# dmxisolator-mod-v1a.net
KiCad netlist of a schematic drawn in EAGLE
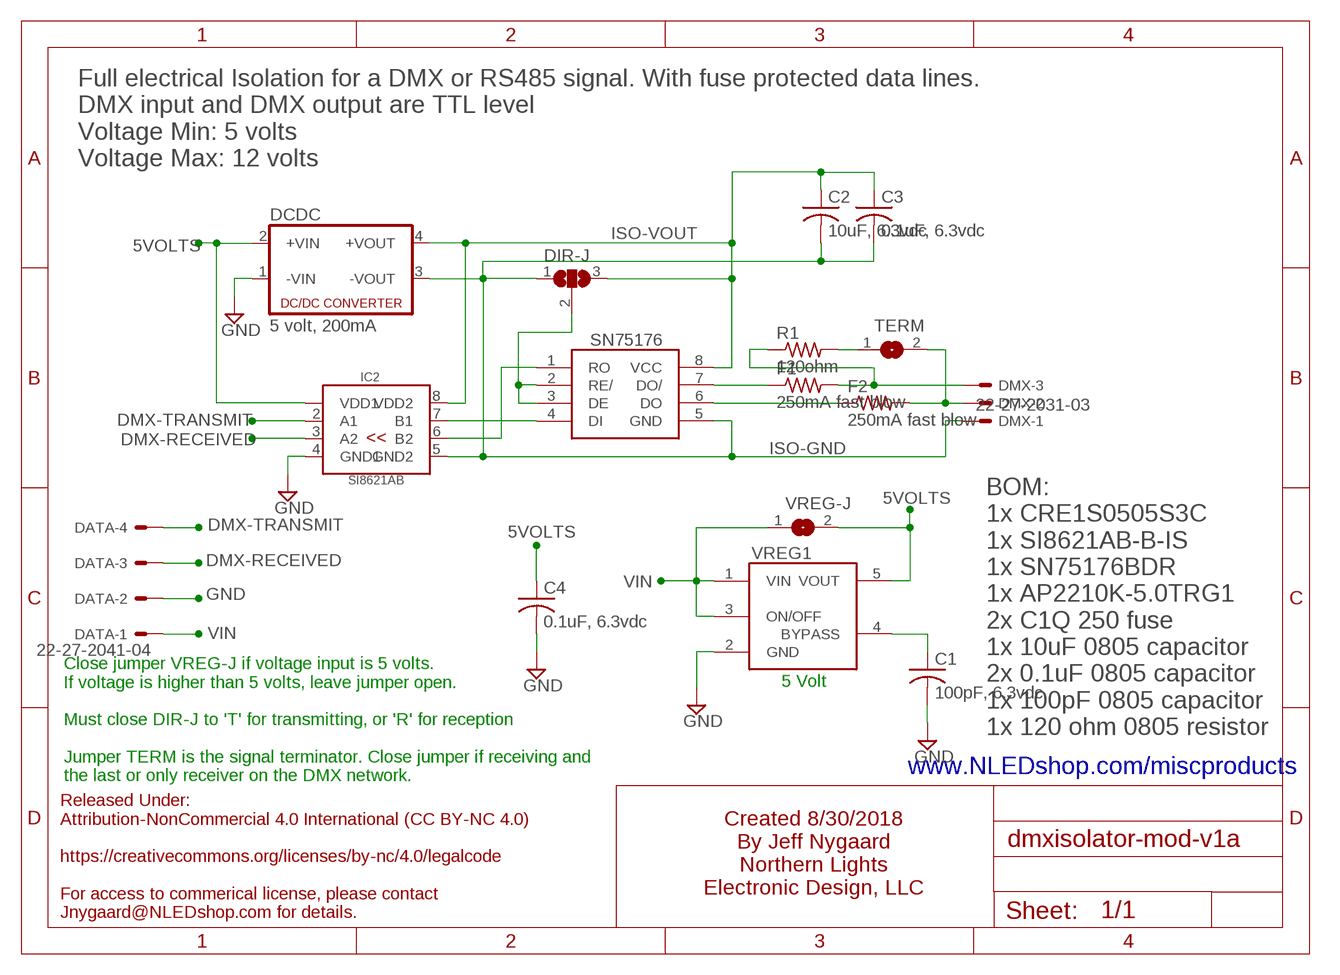
[diagram p0: schematic, sheet 1]

(export (version "E")
  (design (tool "Eeschema 10.0.6"))
  (components
    (comp (ref "C1")
      (value "100pF, 6.3vdc")
      (footprint "eagle-import:C0805")
      (libsource (lib "eagle-import") (part "C-USC0805"))
    )
    (comp (ref "C2")
      (value "10uF, 6.3vdc")
      (footprint "eagle-import:C0805")
      (libsource (lib "eagle-import") (part "C-USC0805"))
    )
    (comp (ref "C3")
      (value "0.1uF, 6.3vdc")
      (footprint "eagle-import:C0805")
      (libsource (lib "eagle-import") (part "C-USC0805"))
    )
    (comp (ref "C4")
      (value "0.1uF, 6.3vdc")
      (footprint "eagle-import:C0805")
      (libsource (lib "eagle-import") (part "C-USC0805"))
    )
    (comp (ref "DATA")
      (value "22-27-2041-04")
      (footprint "eagle-import:6410-04")
      (fields (field (name "MF") "MOLEX"))
      (libsource (lib "eagle-import") (part "22-?-0427-2041"))
    )
    (comp (ref "DCDC")
      (value "5 volt, 200mA")
      (footprint "eagle-import:NME")
      (fields (field (name "MF") "C & D TECHNOLOGIES, INC") (field (name "MPN") "NME1205D"))
      (libsource (lib "eagle-import") (part "NME"))
    )
    (comp (ref "DIR-J")
      (value "SJ2W")
      (footprint "eagle-import:SJ_2")
      (libsource (lib "eagle-import") (part "SJ2W"))
    )
    (comp (ref "DMX")
      (value "22-27-2031-03")
      (footprint "eagle-import:6410-03")
      (fields (field (name "MF") "MOLEX"))
      (libsource (lib "eagle-import") (part "22-?-0327-2031"))
    )
    (comp (ref "F1")
      (value "250mA fast blow")
      (footprint "eagle-import:R1206")
      (libsource (lib "eagle-import") (part "R-US_R1206"))
    )
    (comp (ref "F2")
      (value "250mA fast blow")
      (footprint "eagle-import:R1206")
      (libsource (lib "eagle-import") (part "R-US_R1206"))
    )
    (comp (ref "IC2")
      (value "SI8621AB-B-IS")
      (footprint "eagle-import:SOIC-8")
      (libsource (lib "eagle-import") (part "SI8621AB-B-IS"))
    )
    (comp (ref "R1")
      (value "120ohm")
      (footprint "eagle-import:R0805")
      (libsource (lib "eagle-import") (part "R-US_R0805"))
    )
    (comp (ref "SN75176")
      (value "SN75176SMD")
      (footprint "eagle-import:SOIC-8")
      (libsource (lib "eagle-import") (part "SN75176SMD"))
    )
    (comp (ref "TERM")
      (value "SJ")
      (footprint "eagle-import:SJ")
      (libsource (lib "eagle-import") (part "SJ"))
    )
    (comp (ref "VREG-J")
      (value "SJ")
      (footprint "eagle-import:SJ")
      (libsource (lib "eagle-import") (part "SJ"))
    )
    (comp (ref "VREG1")
      (value "AP2210K")
      (footprint "eagle-import:SOT25")
      (libsource (lib "eagle-import") (part "AP2210K"))
    )
  )
  (nets
    (net (code "1") (name "/5VOLTS") (class "Default")
      (node (ref "C4") (pin "1") (pinfunction "1_1") (pintype "passive"))
      (node (ref "DCDC") (pin "2") (pinfunction "+VIN_2") (pintype "passive"))
      (node (ref "IC2") (pin "1") (pinfunction "VDD1_1") (pintype "bidirectional"))
      (node (ref "VREG-J") (pin "2") (pinfunction "2_2") (pintype "passive"))
      (node (ref "VREG1") (pin "5") (pinfunction "VOUT_5") (pintype "power_in"))
    )
    (net (code "2") (name "/DMX-RECEIVED") (class "Default")
      (node (ref "DATA") (pin "3") (pinfunction "S_3") (pintype "passive"))
      (node (ref "IC2") (pin "3") (pinfunction "A2_3") (pintype "bidirectional"))
    )
    (net (code "3") (name "/DMX-TRANSMIT") (class "Default")
      (node (ref "DATA") (pin "4") (pinfunction "S_4") (pintype "passive"))
      (node (ref "IC2") (pin "2") (pinfunction "A1_2") (pintype "bidirectional"))
    )
    (net (code "4") (name "/ISO-GND") (class "Default")
      (node (ref "C2") (pin "2") (pinfunction "2_2") (pintype "passive"))
      (node (ref "C3") (pin "2") (pinfunction "2_2") (pintype "passive"))
      (node (ref "DCDC") (pin "3") (pinfunction "-VOUT_3") (pintype "passive"))
      (node (ref "DIR-J") (pin "1") (pinfunction "1_1") (pintype "passive"))
      (node (ref "DMX") (pin "1") (pinfunction "S_1") (pintype "passive"))
      (node (ref "IC2") (pin "5") (pinfunction "GND2_5") (pintype "bidirectional"))
      (node (ref "SN75176") (pin "5") (pinfunction "GND_5") (pintype "bidirectional"))
    )
    (net (code "5") (name "/ISO-VOUT") (class "Default")
      (node (ref "C2") (pin "1") (pinfunction "1_1") (pintype "passive"))
      (node (ref "C3") (pin "1") (pinfunction "1_1") (pintype "passive"))
      (node (ref "DCDC") (pin "4") (pinfunction "+VOUT_4") (pintype "passive"))
      (node (ref "DIR-J") (pin "3") (pinfunction "3_3") (pintype "passive"))
      (node (ref "IC2") (pin "8") (pinfunction "VDD2_8") (pintype "bidirectional"))
      (node (ref "SN75176") (pin "8") (pinfunction "VCC_8") (pintype "bidirectional"))
    )
    (net (code "6") (name "/VIN") (class "Default")
      (node (ref "DATA") (pin "1") (pinfunction "S_1") (pintype "passive"))
      (node (ref "VREG-J") (pin "1") (pinfunction "1_1") (pintype "passive"))
      (node (ref "VREG1") (pin "1") (pinfunction "VIN_1") (pintype "power_in"))
      (node (ref "VREG1") (pin "3") (pinfunction "ON/OFF_3") (pintype "input"))
    )
    (net (code "7") (name "GND") (class "Default")
      (node (ref "C1") (pin "2") (pinfunction "2_2") (pintype "passive"))
      (node (ref "C4") (pin "2") (pinfunction "2_2") (pintype "passive"))
      (node (ref "DATA") (pin "2") (pinfunction "S_2") (pintype "passive"))
      (node (ref "DCDC") (pin "1") (pinfunction "-VIN_1") (pintype "passive"))
      (node (ref "IC2") (pin "4") (pinfunction "GND1_4") (pintype "bidirectional"))
      (node (ref "VREG1") (pin "2") (pinfunction "GND_2") (pintype "power_in"))
    )
    (net (code "8") (name "Net-(DMXB-S)") (class "Default")
      (node (ref "DMX") (pin "2") (pinfunction "S_2") (pintype "passive"))
      (node (ref "F2") (pin "2") (pinfunction "2_2") (pintype "passive"))
      (node (ref "TERM") (pin "2") (pinfunction "2_2") (pintype "passive"))
    )
    (net (code "9") (name "Net-(DMXC-S)") (class "Default")
      (node (ref "DMX") (pin "3") (pinfunction "S_3") (pintype "passive"))
      (node (ref "F1") (pin "2") (pinfunction "2_2") (pintype "passive"))
      (node (ref "R1") (pin "1") (pinfunction "1_1") (pintype "passive"))
    )
    (net (code "10") (name "Net-(IC2-B1)") (class "Default")
      (node (ref "IC2") (pin "7") (pinfunction "B1_7") (pintype "bidirectional"))
      (node (ref "SN75176") (pin "4") (pinfunction "DI_4") (pintype "bidirectional"))
    )
    (net (code "11") (name "Net-(IC2-B2)") (class "Default")
      (node (ref "IC2") (pin "6") (pinfunction "B2_6") (pintype "bidirectional"))
      (node (ref "SN75176") (pin "1") (pinfunction "RO_1") (pintype "bidirectional"))
    )
    (net (code "12") (name "Net-(R1-Pad2)") (class "Default")
      (node (ref "R1") (pin "2") (pinfunction "2_2") (pintype "passive"))
      (node (ref "TERM") (pin "1") (pinfunction "1_1") (pintype "passive"))
    )
    (net (code "13") (name "Net-(SN75176-DE)") (class "Default")
      (node (ref "DIR-J") (pin "2") (pinfunction "2_2") (pintype "passive"))
      (node (ref "SN75176") (pin "2") (pinfunction "RE/_2") (pintype "bidirectional"))
      (node (ref "SN75176") (pin "3") (pinfunction "DE_3") (pintype "bidirectional"))
    )
    (net (code "14") (name "Net-(SN75176-DO)") (class "Default")
      (node (ref "F2") (pin "1") (pinfunction "1_1") (pintype "passive"))
      (node (ref "SN75176") (pin "6") (pinfunction "DO_6") (pintype "bidirectional"))
    )
    (net (code "15") (name "Net-(SN75176-DO{slash})") (class "Default")
      (node (ref "F1") (pin "1") (pinfunction "1_1") (pintype "passive"))
      (node (ref "SN75176") (pin "7") (pinfunction "DO/_7") (pintype "bidirectional"))
    )
    (net (code "16") (name "Net-(VREG1-BYPASS)") (class "Default")
      (node (ref "C1") (pin "1") (pinfunction "1_1") (pintype "passive"))
      (node (ref "VREG1") (pin "4") (pinfunction "BYPASS_4") (pintype "power_in"))
    )
  )
)
